# gps_daughter_board.net
KiCad netlist of a schematic drawn in EAGLE
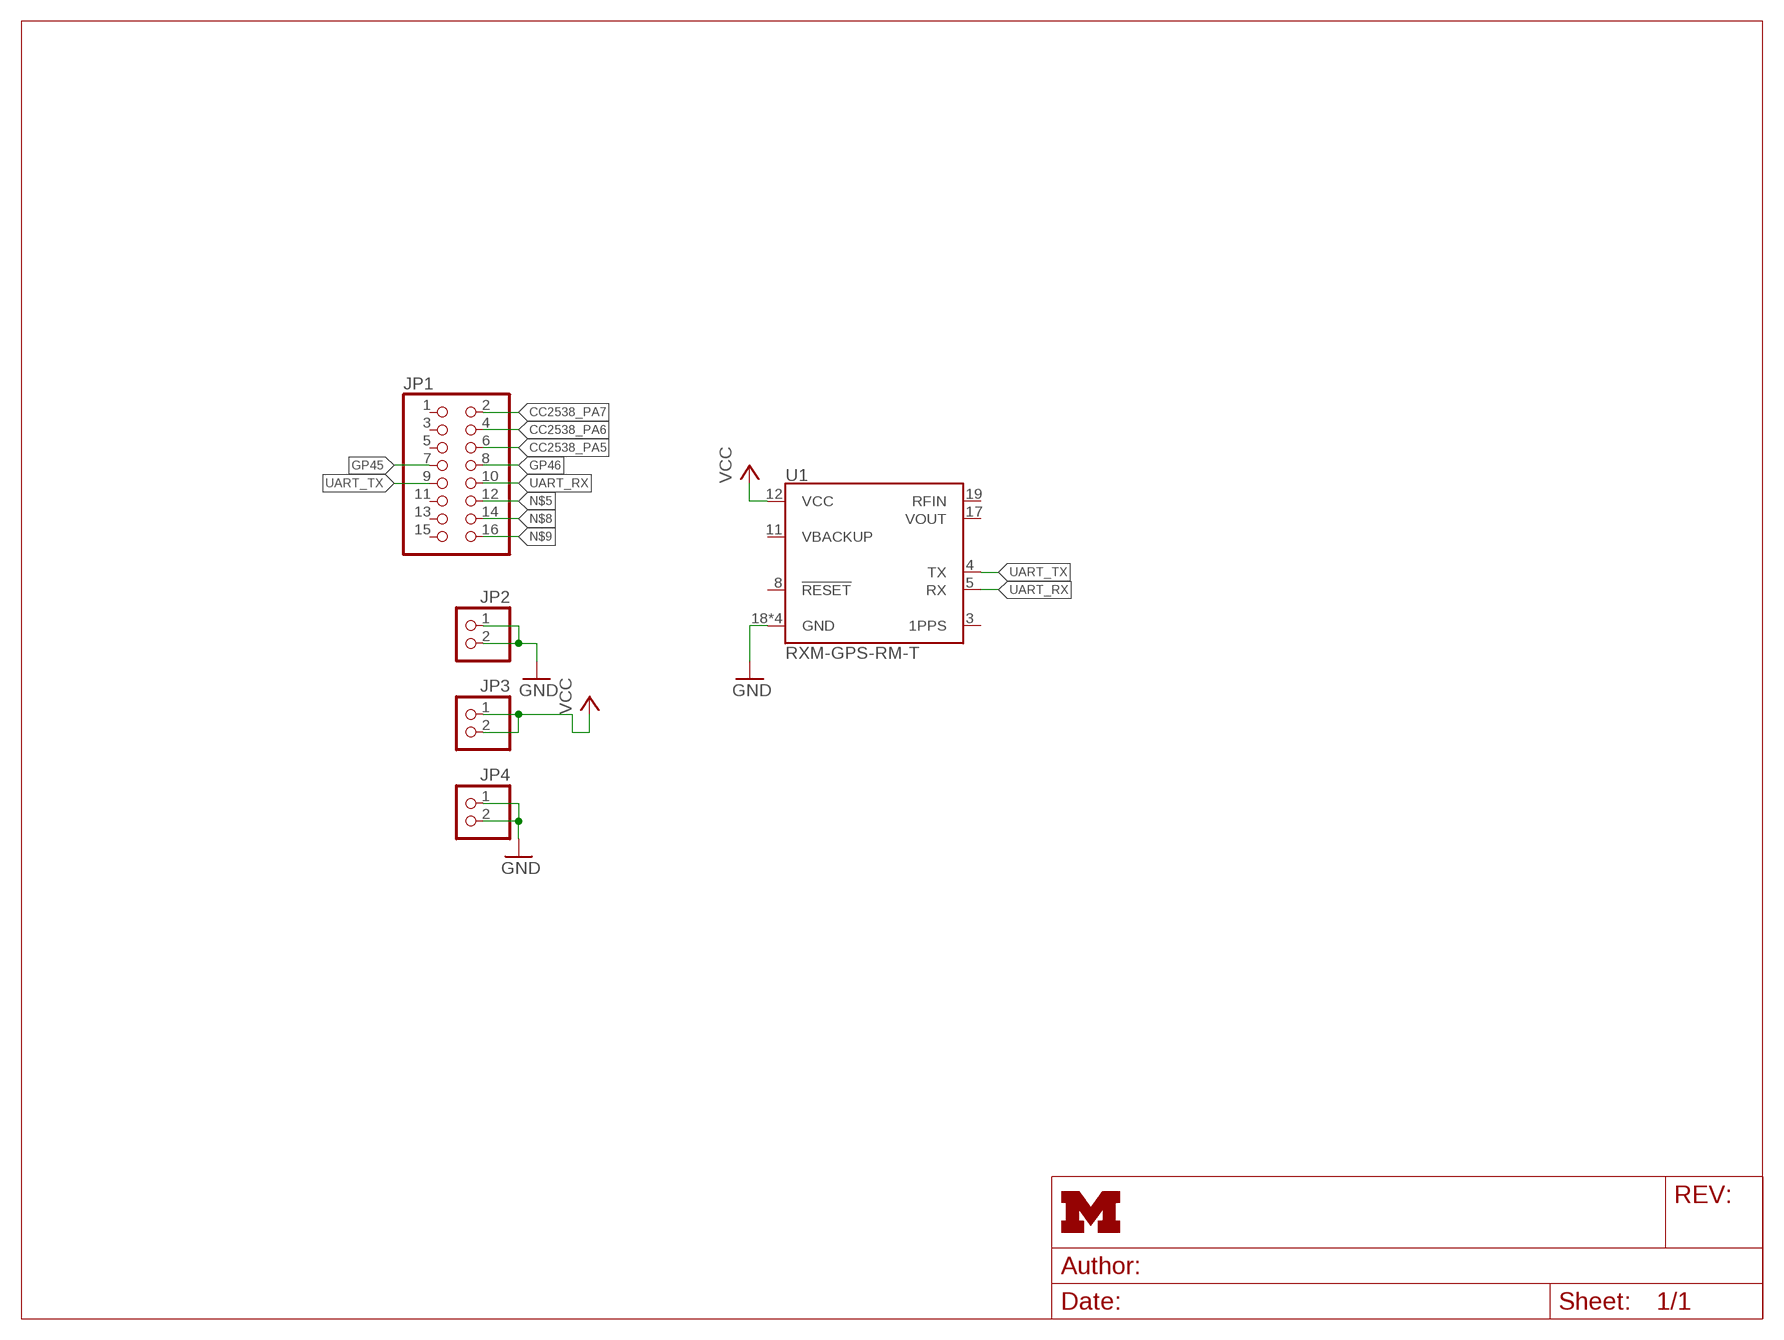
[diagram p0: schematic, sheet 1]

(export (version "E")
  (design (tool "Eeschema 10.0.6"))
  (components
    (comp (ref "JP1")
      (value "PINHD-2X8")
      (footprint "eagle-import:2X08")
      (libsource (lib "eagle-import") (part "PINHD-2X8"))
    )
    (comp (ref "JP2")
      (value "PINHD-1X2")
      (footprint "eagle-import:1X02")
      (libsource (lib "eagle-import") (part "PINHD-1X2"))
    )
    (comp (ref "JP3")
      (value "PINHD-1X2")
      (footprint "eagle-import:1X02")
      (libsource (lib "eagle-import") (part "PINHD-1X2"))
    )
    (comp (ref "JP4")
      (value "PINHD-1X2")
      (footprint "eagle-import:1X02")
      (libsource (lib "eagle-import") (part "PINHD-1X2"))
    )
    (comp (ref "U1")
      (value "RXM-GPS-RM-T")
      (footprint "eagle-import:RXM-GPS-RM-T")
      (libsource (lib "eagle-import") (part "RXM-GPS-RM-T"))
    )
  )
  (nets
    (net (code "1") (name "CC2538_PA5") (class "Default")
      (node (ref "JP1") (pin "6") (pinfunction "6_6") (pintype "passive"))
    )
    (net (code "2") (name "CC2538_PA6") (class "Default")
      (node (ref "JP1") (pin "4") (pinfunction "4_4") (pintype "passive"))
    )
    (net (code "3") (name "CC2538_PA7") (class "Default")
      (node (ref "JP1") (pin "2") (pinfunction "2_2") (pintype "passive"))
    )
    (net (code "4") (name "GND") (class "Default")
      (node (ref "JP2") (pin "1") (pinfunction "1_1") (pintype "passive"))
      (node (ref "JP2") (pin "2") (pinfunction "2_2") (pintype "passive"))
      (node (ref "JP4") (pin "1") (pinfunction "1_1") (pintype "passive"))
      (node (ref "JP4") (pin "2") (pinfunction "2_2") (pintype "passive"))
      (node (ref "U1") (pin "18") (pinfunction "GND_18") (pintype "bidirectional"))
      (node (ref "U1") (pin "20") (pinfunction "GND_20") (pintype "bidirectional"))
      (node (ref "U1") (pin "21") (pinfunction "GND_21") (pintype "bidirectional"))
      (node (ref "U1") (pin "22") (pinfunction "GND_22") (pintype "bidirectional"))
    )
    (net (code "5") (name "GP45") (class "Default")
      (node (ref "JP1") (pin "7") (pinfunction "7_7") (pintype "passive"))
    )
    (net (code "6") (name "GP46") (class "Default")
      (node (ref "JP1") (pin "8") (pinfunction "8_8") (pintype "passive"))
    )
    (net (code "7") (name "N$5") (class "Default")
      (node (ref "JP1") (pin "12") (pinfunction "12_12") (pintype "passive"))
    )
    (net (code "8") (name "N$8") (class "Default")
      (node (ref "JP1") (pin "14") (pinfunction "14_14") (pintype "passive"))
    )
    (net (code "9") (name "N$9") (class "Default")
      (node (ref "JP1") (pin "16") (pinfunction "16_16") (pintype "passive"))
    )
    (net (code "10") (name "UART_RX") (class "Default")
      (node (ref "JP1") (pin "10") (pinfunction "10_10") (pintype "passive"))
      (node (ref "U1") (pin "5") (pinfunction "RX_5") (pintype "bidirectional"))
    )
    (net (code "11") (name "UART_TX") (class "Default")
      (node (ref "JP1") (pin "9") (pinfunction "9_9") (pintype "passive"))
      (node (ref "U1") (pin "4") (pinfunction "TX_4") (pintype "bidirectional"))
    )
    (net (code "12") (name "VCC") (class "Default")
      (node (ref "JP3") (pin "1") (pinfunction "1_1") (pintype "passive"))
      (node (ref "JP3") (pin "2") (pinfunction "2_2") (pintype "passive"))
      (node (ref "U1") (pin "12") (pinfunction "VCC_12") (pintype "bidirectional"))
    )
    (net (code "13") (name "unconnected-(JP1-Pad1)") (class "Default")
      (node (ref "JP1") (pin "1") (pinfunction "1_1") (pintype "passive"))
    )
    (net (code "14") (name "unconnected-(JP1-Pad3)") (class "Default")
      (node (ref "JP1") (pin "3") (pinfunction "3_3") (pintype "passive"))
    )
    (net (code "15") (name "unconnected-(JP1-Pad5)") (class "Default")
      (node (ref "JP1") (pin "5") (pinfunction "5_5") (pintype "passive"))
    )
    (net (code "16") (name "unconnected-(JP1-Pad11)") (class "Default")
      (node (ref "JP1") (pin "11") (pinfunction "11_11") (pintype "passive"))
    )
    (net (code "17") (name "unconnected-(JP1-Pad13)") (class "Default")
      (node (ref "JP1") (pin "13") (pinfunction "13_13") (pintype "passive"))
    )
    (net (code "18") (name "unconnected-(JP1-Pad15)") (class "Default")
      (node (ref "JP1") (pin "15") (pinfunction "15_15") (pintype "passive"))
    )
    (net (code "19") (name "unconnected-(U1-1PPS-Pad3)") (class "Default")
      (node (ref "U1") (pin "3") (pinfunction "1PPS_3") (pintype "bidirectional"))
    )
    (net (code "20") (name "unconnected-(U1-RFIN-Pad19)") (class "Default")
      (node (ref "U1") (pin "19") (pinfunction "RFIN_19") (pintype "bidirectional"))
    )
    (net (code "21") (name "unconnected-(U1-VBACKUP-Pad11)") (class "Default")
      (node (ref "U1") (pin "11") (pinfunction "VBACKUP_11") (pintype "bidirectional"))
    )
    (net (code "22") (name "unconnected-(U1-VOUT-Pad17)") (class "Default")
      (node (ref "U1") (pin "17") (pinfunction "VOUT_17") (pintype "bidirectional"))
    )
    (net (code "23") (name "unconnected-(U1-~{RESET}-Pad8)") (class "Default")
      (node (ref "U1") (pin "8") (pinfunction "~{RESET}_8") (pintype "bidirectional"))
    )
  )
)
